# Analog_Front_End.net
KiCad netlist of a schematic drawn in Altium Designer
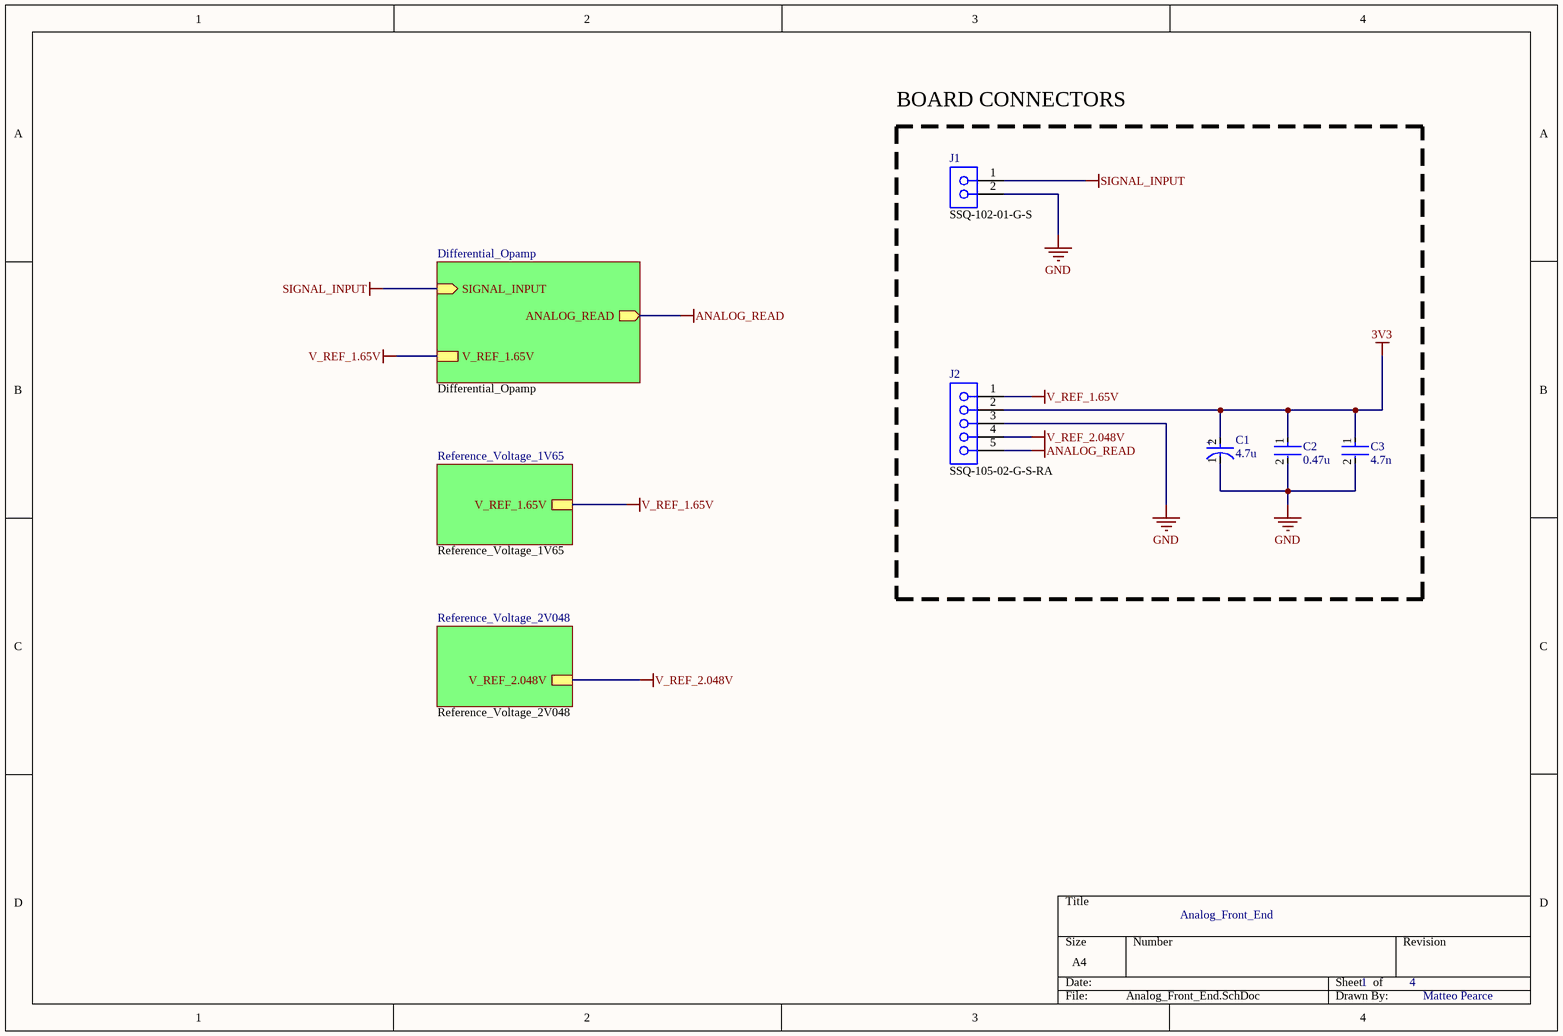
[diagram p0: Analog_Front_End.SchDoc]

(export (version "E")
  (design (tool "Eeschema 10.0.6"))
  (components
    (comp (ref "C1")
      (value "4.7u")
      (footprint "FP-TAJA-MFG")
      (description "4.7uF 20V  ±10% 4Ω 1206  SMD Tantalum Capacitor")
      (fields (field (name "TOLERANCE") "10%") (field (name "VOLTAGE") "20V"))
      (libsource (lib "Altium Content Vault") (part "203bc49f2ac43e59fd269a8c329ed05"))
    )
    (comp (ref "C2")
      (value "0.47u")
      (footprint "FP-GCM188-0_1-IPC_A")
      (description "Ceramic Capacitor for Automotive 470nF  ±10% 16VDC X7R 0603 Paper T/R")
      (fields (field (name "VOLTAGE") "16V") (field (name "TOLERANCE") "10%"))
      (libsource (lib "Altium Content Vault") (part "02cd4be3c70576c341d710602a673aa"))
    )
    (comp (ref "C3")
      (value "4.7n")
      (footprint "FP-CC0805-0_85-MFG")
      (description "CC0805 47 nF X7R 10.00% 50 V")
      (fields (field (name "MANUFACTURER PART NUMBER") "CC0805KRX7R9BB473"))
      (libsource (lib "Altium Content Vault") (part "11868f565c42a9108669ba33697ecf6"))
    )
    (comp (ref "J1")
      (value "SSQ-102-01-G-S")
      (footprint "SMTC-SSQ-102-01-X-S")
      (description "SQ Post Socket, Through-hole, Vertical, -55 to 125 degC, 2.54 mm Pitch, 2-Pin, Female, RoHS")
      (fields (field (name "MANUFACTURER") "Samtec"))
      (libsource (lib "Altium Content Vault") (part "SMTC-SSQ-102-01-X-S"))
    )
    (comp (ref "J2")
      (value "SSQ-105-02-G-S-RA")
      (footprint "SMTC-SSQ-105-02-X-S-RA")
      (description "SQ Post Socket, Through-hole, Right Angle, -55 to 125 degC, 2.54 mm Pitch, 5-Pin, Female, RoHS")
      (fields (field (name "MANUFACTURER") "Samtec"))
      (libsource (lib "Altium Content Vault") (part "SMTC-SSQ-105-02-X-S-RA"))
    )
  )
  (nets
    (net (code "1") (name "3V3") (class "Default")
      (node (ref "C1") (pin "2") (pinfunction "A_2") (pintype "passive"))
      (node (ref "C2") (pin "1") (pinfunction "1_1") (pintype "passive"))
      (node (ref "C3") (pin "1") (pinfunction "1_1") (pintype "passive"))
      (node (ref "J2") (pin "2") (pinfunction "2_2") (pintype "passive"))
    )
    (net (code "2") (name "ANALOG_READ") (class "Default")
      (node (ref "J2") (pin "5") (pinfunction "5_5") (pintype "passive"))
    )
    (net (code "3") (name "GND") (class "Default")
      (node (ref "C1") (pin "1") (pinfunction "C_1") (pintype "passive"))
      (node (ref "C2") (pin "2") (pinfunction "2_2") (pintype "passive"))
      (node (ref "C3") (pin "2") (pinfunction "2_2") (pintype "passive"))
      (node (ref "J1") (pin "2") (pinfunction "2_2") (pintype "passive"))
      (node (ref "J2") (pin "3") (pinfunction "3_3") (pintype "passive"))
    )
    (net (code "4") (name "SIGNAL_INPUT") (class "Default")
      (node (ref "J1") (pin "1") (pinfunction "1_1") (pintype "passive"))
    )
    (net (code "5") (name "V_REF_1.65V") (class "Default")
      (node (ref "J2") (pin "1") (pinfunction "1_1") (pintype "passive"))
    )
    (net (code "6") (name "V_REF_2.048V") (class "Default")
      (node (ref "J2") (pin "4") (pinfunction "4_4") (pintype "passive"))
    )
  )
)
